# pclone-control.net
KiCad netlist of a schematic drawn in EAGLE
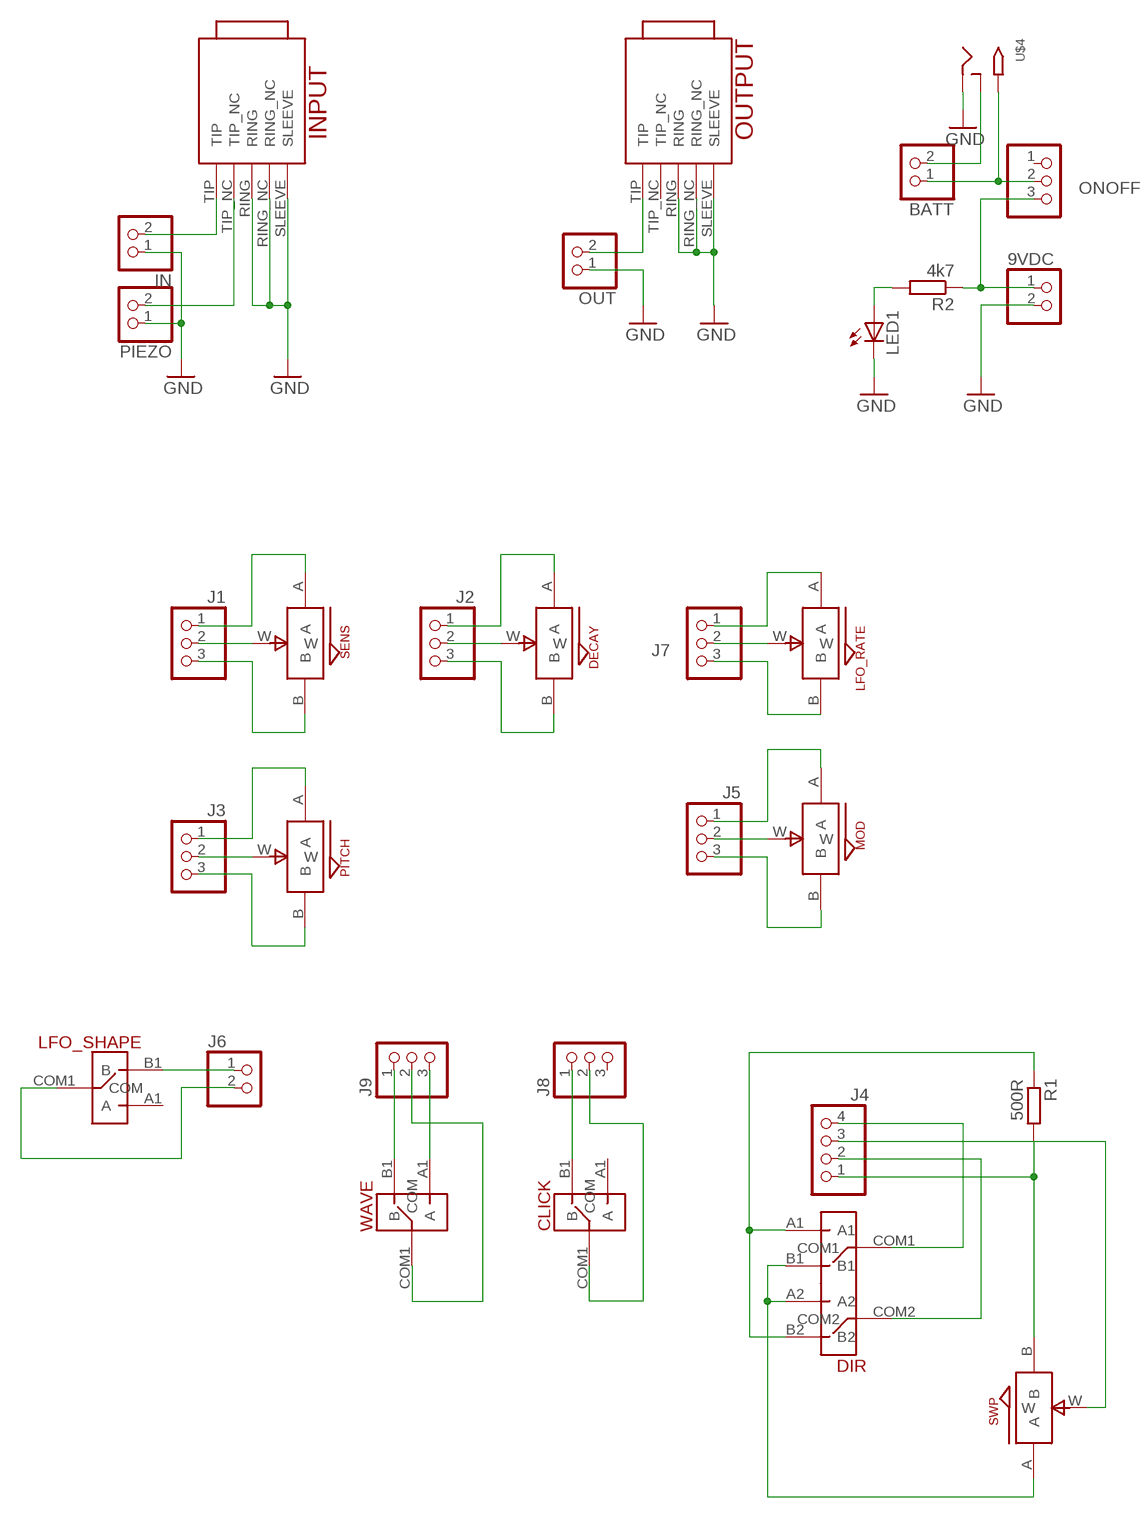
[diagram p0: schematic, sheet 1]

(export (version "E")
  (design (tool "Eeschema 10.0.6"))
  (components
    (comp (ref "9VDC")
      (value "PINHD-1X2")
      (footprint "eagle-import:1X02")
      (libsource (lib "eagle-import") (part "PINHD-1X2"))
    )
    (comp (ref "BATT")
      (value "PINHD-1X2")
      (footprint "eagle-import:1X02")
      (libsource (lib "eagle-import") (part "PINHD-1X2"))
    )
    (comp (ref "CLICK")
      (value "SPDT_SW")
      (footprint "eagle-import:SPDT_SW")
      (libsource (lib "eagle-import") (part "SPDT_SW"))
    )
    (comp (ref "DECAY")
      (value "ALPS_POT_SMALL")
      (footprint "eagle-import:SMALL_ALPS_POT")
      (libsource (lib "eagle-import") (part "ALPS_POT_SMALL"))
    )
    (comp (ref "DIR")
      (value "DPDT_SW")
      (footprint "eagle-import:DPDT_SW")
      (libsource (lib "eagle-import") (part "DPDT_SW"))
    )
    (comp (ref "IN")
      (value "PINHD-1X2")
      (footprint "eagle-import:1X02")
      (libsource (lib "eagle-import") (part "PINHD-1X2"))
    )
    (comp (ref "INPUT")
      (value "TRUCONNECTJACK")
      (footprint "eagle-import:TRUCONNECTJACK")
      (libsource (lib "eagle-import") (part "TRUCONNECTJACK"))
    )
    (comp (ref "J1")
      (value "PINHD-1X3")
      (footprint "eagle-import:1X03")
      (libsource (lib "eagle-import") (part "PINHD-1X3"))
    )
    (comp (ref "J2")
      (value "PINHD-1X3")
      (footprint "eagle-import:1X03")
      (libsource (lib "eagle-import") (part "PINHD-1X3"))
    )
    (comp (ref "J3")
      (value "PINHD-1X3")
      (footprint "eagle-import:1X03")
      (libsource (lib "eagle-import") (part "PINHD-1X3"))
    )
    (comp (ref "J4")
      (value "PINHD-1X4")
      (footprint "eagle-import:1X04")
      (libsource (lib "eagle-import") (part "PINHD-1X4"))
    )
    (comp (ref "J5")
      (value "PINHD-1X3")
      (footprint "eagle-import:1X03")
      (libsource (lib "eagle-import") (part "PINHD-1X3"))
    )
    (comp (ref "J6")
      (value "PINHD-1X2")
      (footprint "eagle-import:1X02")
      (libsource (lib "eagle-import") (part "PINHD-1X2"))
    )
    (comp (ref "J7")
      (value "PINHD-1X3")
      (footprint "eagle-import:1X03")
      (libsource (lib "eagle-import") (part "PINHD-1X3"))
    )
    (comp (ref "J8")
      (value "PINHD-1X3")
      (footprint "eagle-import:1X03")
      (libsource (lib "eagle-import") (part "PINHD-1X3"))
    )
    (comp (ref "J9")
      (value "PINHD-1X3")
      (footprint "eagle-import:1X03")
      (libsource (lib "eagle-import") (part "PINHD-1X3"))
    )
    (comp (ref "LED1")
      (value "LED3MM")
      (footprint "eagle-import:LED3MM")
      (libsource (lib "eagle-import") (part "LED3MM"))
    )
    (comp (ref "LFO_RATE")
      (value "ALPS_POT_SMALL")
      (footprint "eagle-import:SMALL_ALPS_POT")
      (libsource (lib "eagle-import") (part "ALPS_POT_SMALL"))
    )
    (comp (ref "LFO_SHAPE")
      (value "SPDT_SW")
      (footprint "eagle-import:SPDT_SW")
      (libsource (lib "eagle-import") (part "SPDT_SW"))
    )
    (comp (ref "MOD")
      (value "ALPS_POT_SMALL")
      (footprint "eagle-import:SMALL_ALPS_POT")
      (libsource (lib "eagle-import") (part "ALPS_POT_SMALL"))
    )
    (comp (ref "ONOFF")
      (value "PINHD-1X3")
      (footprint "eagle-import:1X03")
      (libsource (lib "eagle-import") (part "PINHD-1X3"))
    )
    (comp (ref "OUT")
      (value "PINHD-1X2")
      (footprint "eagle-import:1X02")
      (libsource (lib "eagle-import") (part "PINHD-1X2"))
    )
    (comp (ref "OUTPUT")
      (value "TRUCONNECTJACK")
      (footprint "eagle-import:TRUCONNECTJACK")
      (libsource (lib "eagle-import") (part "TRUCONNECTJACK"))
    )
    (comp (ref "PIEZO")
      (value "PINHD-1X2")
      (footprint "eagle-import:1X02")
      (libsource (lib "eagle-import") (part "PINHD-1X2"))
    )
    (comp (ref "PITCH")
      (value "ALPS_POT_SMALL")
      (footprint "eagle-import:SMALL_ALPS_POT")
      (libsource (lib "eagle-import") (part "ALPS_POT_SMALL"))
    )
    (comp (ref "R1")
      (value "500R")
      (footprint "eagle-import:0207_7")
      (libsource (lib "eagle-import") (part "R-EU_0207/7"))
    )
    (comp (ref "R2")
      (value "4k7")
      (footprint "eagle-import:0207_7")
      (libsource (lib "eagle-import") (part "R-EU_0207/7"))
    )
    (comp (ref "SENS")
      (value "ALPS_POT_SMALL")
      (footprint "eagle-import:SMALL_ALPS_POT")
      (libsource (lib "eagle-import") (part "ALPS_POT_SMALL"))
    )
    (comp (ref "SWP")
      (value "ALPS_POT_SMALL")
      (footprint "eagle-import:SMALL_ALPS_POT")
      (libsource (lib "eagle-import") (part "ALPS_POT_SMALL"))
    )
    (comp (ref "U$4")
      (value "2.1MMJACKTHM")
      (footprint "eagle-import:PJ-102A")
      (libsource (lib "eagle-import") (part "2.1MMJACKTHM"))
    )
    (comp (ref "WAVE")
      (value "SPDT_SW")
      (footprint "eagle-import:SPDT_SW")
      (libsource (lib "eagle-import") (part "SPDT_SW"))
    )
  )
  (nets
    (net (code "1") (name "GND") (class "Default")
      (node (ref "9VDC") (pin "2") (pinfunction "2_2") (pintype "passive"))
      (node (ref "IN") (pin "1") (pinfunction "1_1") (pintype "passive"))
      (node (ref "INPUT") (pin "RING") (pinfunction "RING_RING") (pintype "bidirectional"))
      (node (ref "INPUT") (pin "RING_NC") (pinfunction "RING_NC_RING_NC") (pintype "bidirectional"))
      (node (ref "INPUT") (pin "SLEEVE") (pinfunction "SLEEVE_SLEEVE") (pintype "bidirectional"))
      (node (ref "J1") (pin "1") (pinfunction "1_1") (pintype "passive"))
      (node (ref "LED1") (pin "K") (pinfunction "C_K") (pintype "passive"))
      (node (ref "OUT") (pin "1") (pinfunction "1_1") (pintype "passive"))
      (node (ref "OUTPUT") (pin "RING") (pinfunction "RING_RING") (pintype "bidirectional"))
      (node (ref "OUTPUT") (pin "RING_NC") (pinfunction "RING_NC_RING_NC") (pintype "bidirectional"))
      (node (ref "OUTPUT") (pin "SLEEVE") (pinfunction "SLEEVE_SLEEVE") (pintype "bidirectional"))
      (node (ref "PIEZO") (pin "1") (pinfunction "1_1") (pintype "passive"))
      (node (ref "SENS") (pin "A") (pinfunction "A_A") (pintype "bidirectional"))
      (node (ref "U$4") (pin "RING") (pinfunction "RING_RING") (pintype "bidirectional"))
    )
    (net (code "2") (name "Net-(9VDC-Pad1)") (class "Default")
      (node (ref "9VDC") (pin "1") (pinfunction "1_1") (pintype "passive"))
      (node (ref "ONOFF") (pin "3") (pinfunction "3_3") (pintype "passive"))
      (node (ref "R2") (pin "1") (pinfunction "1_1") (pintype "passive"))
    )
    (net (code "3") (name "Net-(BATT-Pad1)") (class "Default")
      (node (ref "BATT") (pin "1") (pinfunction "1_1") (pintype "passive"))
      (node (ref "ONOFF") (pin "2") (pinfunction "2_2") (pintype "passive"))
      (node (ref "U$4") (pin "TIP") (pinfunction "TIP_TIP") (pintype "bidirectional"))
    )
    (net (code "4") (name "Net-(BATT-Pad2)") (class "Default")
      (node (ref "BATT") (pin "2") (pinfunction "2_2") (pintype "passive"))
      (node (ref "U$4") (pin "RING_SW") (pinfunction "RING_SW_RING_SW") (pintype "bidirectional"))
    )
    (net (code "5") (name "Net-(CLICK-B)") (class "Default")
      (node (ref "CLICK") (pin "B1") (pinfunction "B_B1") (pintype "bidirectional"))
      (node (ref "J8") (pin "1") (pinfunction "1_1") (pintype "passive"))
    )
    (net (code "6") (name "Net-(CLICK-COM)") (class "Default")
      (node (ref "CLICK") (pin "COM1") (pinfunction "COM_COM1") (pintype "bidirectional"))
      (node (ref "J8") (pin "2") (pinfunction "2_2") (pintype "passive"))
    )
    (net (code "7") (name "Net-(DECAY-PadA)") (class "Default")
      (node (ref "DECAY") (pin "A") (pinfunction "A_A") (pintype "bidirectional"))
      (node (ref "J2") (pin "1") (pinfunction "1_1") (pintype "passive"))
    )
    (net (code "8") (name "Net-(DECAY-PadB)") (class "Default")
      (node (ref "DECAY") (pin "B") (pinfunction "B_B") (pintype "bidirectional"))
      (node (ref "J2") (pin "3") (pinfunction "3_3") (pintype "passive"))
    )
    (net (code "9") (name "Net-(DECAY-PadW)") (class "Default")
      (node (ref "DECAY") (pin "W") (pinfunction "W_W") (pintype "bidirectional"))
      (node (ref "J2") (pin "2") (pinfunction "2_2") (pintype "passive"))
    )
    (net (code "10") (name "Net-(DIR-PadA1)") (class "Default")
      (node (ref "DIR") (pin "A1") (pinfunction "A1_A1") (pintype "bidirectional"))
      (node (ref "DIR") (pin "B2") (pinfunction "B2_B2") (pintype "bidirectional"))
      (node (ref "R1") (pin "1") (pinfunction "1_1") (pintype "passive"))
    )
    (net (code "11") (name "Net-(DIR-PadA2)") (class "Default")
      (node (ref "DIR") (pin "A2") (pinfunction "A2_A2") (pintype "bidirectional"))
      (node (ref "DIR") (pin "B1") (pinfunction "B1_B1") (pintype "bidirectional"))
      (node (ref "SWP") (pin "A") (pinfunction "A_A") (pintype "bidirectional"))
    )
    (net (code "12") (name "Net-(DIR-PadCOM1)") (class "Default")
      (node (ref "DIR") (pin "COM1") (pinfunction "COM1_COM1") (pintype "bidirectional"))
      (node (ref "J4") (pin "4") (pinfunction "4_4") (pintype "passive"))
    )
    (net (code "13") (name "Net-(DIR-PadCOM2)") (class "Default")
      (node (ref "DIR") (pin "COM2") (pinfunction "COM2_COM2") (pintype "bidirectional"))
      (node (ref "J4") (pin "2") (pinfunction "2_2") (pintype "passive"))
    )
    (net (code "14") (name "Net-(IN-Pad2)") (class "Default")
      (node (ref "IN") (pin "2") (pinfunction "2_2") (pintype "passive"))
      (node (ref "INPUT") (pin "TIP") (pinfunction "TIP_TIP") (pintype "bidirectional"))
    )
    (net (code "15") (name "Net-(INPUT-PadTIP_NC)") (class "Default")
      (node (ref "INPUT") (pin "TIP_NC") (pinfunction "TIP_NC_TIP_NC") (pintype "bidirectional"))
      (node (ref "PIEZO") (pin "2") (pinfunction "2_2") (pintype "passive"))
    )
    (net (code "16") (name "Net-(J1-Pad2)") (class "Default")
      (node (ref "J1") (pin "2") (pinfunction "2_2") (pintype "passive"))
      (node (ref "SENS") (pin "W") (pinfunction "W_W") (pintype "bidirectional"))
    )
    (net (code "17") (name "Net-(J1-Pad3)") (class "Default")
      (node (ref "J1") (pin "3") (pinfunction "3_3") (pintype "passive"))
      (node (ref "SENS") (pin "B") (pinfunction "B_B") (pintype "bidirectional"))
    )
    (net (code "18") (name "Net-(J3-Pad1)") (class "Default")
      (node (ref "J3") (pin "1") (pinfunction "1_1") (pintype "passive"))
      (node (ref "PITCH") (pin "A") (pinfunction "A_A") (pintype "bidirectional"))
    )
    (net (code "19") (name "Net-(J3-Pad2)") (class "Default")
      (node (ref "J3") (pin "2") (pinfunction "2_2") (pintype "passive"))
      (node (ref "PITCH") (pin "W") (pinfunction "W_W") (pintype "bidirectional"))
    )
    (net (code "20") (name "Net-(J3-Pad3)") (class "Default")
      (node (ref "J3") (pin "3") (pinfunction "3_3") (pintype "passive"))
      (node (ref "PITCH") (pin "B") (pinfunction "B_B") (pintype "bidirectional"))
    )
    (net (code "21") (name "Net-(J4-Pad1)") (class "Default")
      (node (ref "J4") (pin "1") (pinfunction "1_1") (pintype "passive"))
      (node (ref "R1") (pin "2") (pinfunction "2_2") (pintype "passive"))
      (node (ref "SWP") (pin "B") (pinfunction "B_B") (pintype "bidirectional"))
    )
    (net (code "22") (name "Net-(J4-Pad3)") (class "Default")
      (node (ref "J4") (pin "3") (pinfunction "3_3") (pintype "passive"))
      (node (ref "SWP") (pin "W") (pinfunction "W_W") (pintype "bidirectional"))
    )
    (net (code "23") (name "Net-(J5-Pad1)") (class "Default")
      (node (ref "J5") (pin "1") (pinfunction "1_1") (pintype "passive"))
      (node (ref "MOD") (pin "A") (pinfunction "A_A") (pintype "bidirectional"))
    )
    (net (code "24") (name "Net-(J5-Pad2)") (class "Default")
      (node (ref "J5") (pin "2") (pinfunction "2_2") (pintype "passive"))
      (node (ref "MOD") (pin "W") (pinfunction "W_W") (pintype "bidirectional"))
    )
    (net (code "25") (name "Net-(J5-Pad3)") (class "Default")
      (node (ref "J5") (pin "3") (pinfunction "3_3") (pintype "passive"))
      (node (ref "MOD") (pin "B") (pinfunction "B_B") (pintype "bidirectional"))
    )
    (net (code "26") (name "Net-(J7-Pad1)") (class "Default")
      (node (ref "J7") (pin "1") (pinfunction "1_1") (pintype "passive"))
      (node (ref "LFO_RATE") (pin "A") (pinfunction "A_A") (pintype "bidirectional"))
    )
    (net (code "27") (name "Net-(J7-Pad2)") (class "Default")
      (node (ref "J7") (pin "2") (pinfunction "2_2") (pintype "passive"))
      (node (ref "LFO_RATE") (pin "W") (pinfunction "W_W") (pintype "bidirectional"))
    )
    (net (code "28") (name "Net-(J7-Pad3)") (class "Default")
      (node (ref "J7") (pin "3") (pinfunction "3_3") (pintype "passive"))
      (node (ref "LFO_RATE") (pin "B") (pinfunction "B_B") (pintype "bidirectional"))
    )
    (net (code "29") (name "Net-(LED1-PadA)") (class "Default")
      (node (ref "LED1") (pin "A") (pinfunction "A_A") (pintype "passive"))
      (node (ref "R2") (pin "2") (pinfunction "2_2") (pintype "passive"))
    )
    (net (code "30") (name "Net-(LFO_SHAPE-B)") (class "Default")
      (node (ref "J6") (pin "1") (pinfunction "1_1") (pintype "passive"))
      (node (ref "LFO_SHAPE") (pin "B1") (pinfunction "B_B1") (pintype "bidirectional"))
    )
    (net (code "31") (name "Net-(LFO_SHAPE-COM)") (class "Default")
      (node (ref "J6") (pin "2") (pinfunction "2_2") (pintype "passive"))
      (node (ref "LFO_SHAPE") (pin "COM1") (pinfunction "COM_COM1") (pintype "bidirectional"))
    )
    (net (code "32") (name "Net-(OUT-Pad2)") (class "Default")
      (node (ref "OUT") (pin "2") (pinfunction "2_2") (pintype "passive"))
      (node (ref "OUTPUT") (pin "TIP") (pinfunction "TIP_TIP") (pintype "bidirectional"))
    )
    (net (code "33") (name "Net-(WAVE-A)") (class "Default")
      (node (ref "J9") (pin "3") (pinfunction "3_3") (pintype "passive"))
      (node (ref "WAVE") (pin "A1") (pinfunction "A_A1") (pintype "bidirectional"))
    )
    (net (code "34") (name "Net-(WAVE-B)") (class "Default")
      (node (ref "J9") (pin "1") (pinfunction "1_1") (pintype "passive"))
      (node (ref "WAVE") (pin "B1") (pinfunction "B_B1") (pintype "bidirectional"))
    )
    (net (code "35") (name "Net-(WAVE-COM)") (class "Default")
      (node (ref "J9") (pin "2") (pinfunction "2_2") (pintype "passive"))
      (node (ref "WAVE") (pin "COM1") (pinfunction "COM_COM1") (pintype "bidirectional"))
    )
    (net (code "36") (name "unconnected-(CLICK-A-PadA1)") (class "Default")
      (node (ref "CLICK") (pin "A1") (pinfunction "A_A1") (pintype "bidirectional"))
    )
    (net (code "37") (name "unconnected-(J8-Pad3)") (class "Default")
      (node (ref "J8") (pin "3") (pinfunction "3_3") (pintype "passive"))
    )
    (net (code "38") (name "unconnected-(LFO_SHAPE-A-PadA1)") (class "Default")
      (node (ref "LFO_SHAPE") (pin "A1") (pinfunction "A_A1") (pintype "bidirectional"))
    )
    (net (code "39") (name "unconnected-(ONOFF-Pad1)") (class "Default")
      (node (ref "ONOFF") (pin "1") (pinfunction "1_1") (pintype "passive"))
    )
    (net (code "40") (name "unconnected-(OUTPUT-PadTIP_NC)") (class "Default")
      (node (ref "OUTPUT") (pin "TIP_NC") (pinfunction "TIP_NC_TIP_NC") (pintype "bidirectional"))
    )
  )
)
